# SAM4N_Xplained_Pro_Connectors.net
KiCad netlist of a schematic drawn in Altium Designer
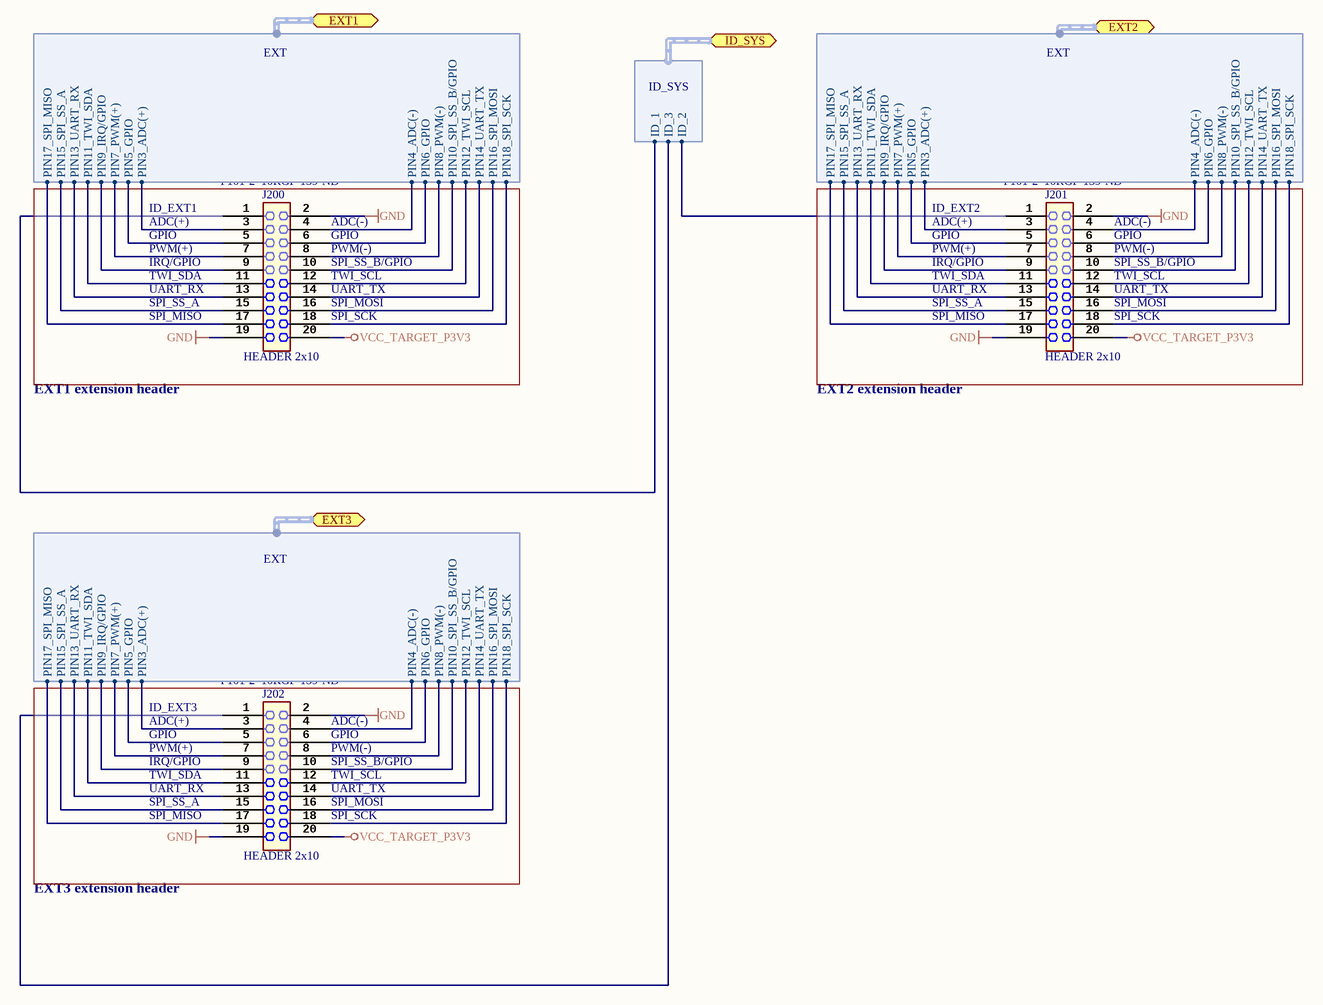
[diagram p0: SAM4N_Xplained_Pro_Connectors.SchDoc]

(export (version "E")
  (design (tool "Eeschema 10.0.6"))
  (components
    (comp (ref "J200")
      (value "HEADER 2x10")
      (footprint "AP8-00622")
      (description "Pin header, 2x10, Right Angle, 2.54mm, THM, Pin In Paste")
      (fields (field (name "ALTIUM_VALUE") "P101-2*10RGF-139-ND") (field (name "MPN") "P101-2*10RGF-139-ND"))
      (libsource (lib "AltiumDbLib") (part "HEADER 2x10"))
    )
    (comp (ref "J201")
      (value "HEADER 2x10")
      (footprint "AP8-00622")
      (description "Pin header, 2x10, Right Angle, 2.54mm, THM, Pin In Paste")
      (fields (field (name "ALTIUM_VALUE") "P101-2*10RGF-139-ND") (field (name "MPN") "P101-2*10RGF-139-ND"))
      (libsource (lib "AltiumDbLib") (part "HEADER 2x10"))
    )
    (comp (ref "J202")
      (value "HEADER 2x10")
      (footprint "AP8-00622")
      (description "Pin header, 2x10, Right Angle, 2.54mm, THM, Pin In Paste")
      (fields (field (name "ALTIUM_VALUE") "P101-2*10RGF-139-ND") (field (name "MPN") "P101-2*10RGF-139-ND"))
      (libsource (lib "AltiumDbLib") (part "HEADER 2x10"))
    )
  )
  (nets
    (net (code "3") (name "/ID_1") (class "Default")
      (node (ref "J200") (pin "1") (pinfunction "1_1") (pintype "passive"))
    )
    (net (code "4") (name "/ID_2") (class "Default")
      (node (ref "J201") (pin "1") (pinfunction "1_1") (pintype "passive"))
    )
    (net (code "5") (name "/ID_3") (class "Default")
      (node (ref "J202") (pin "1") (pinfunction "1_1") (pintype "passive"))
    )
    (net (code "8") (name "GND") (class "Default")
      (node (ref "J200") (pin "19") (pinfunction "19_19") (pintype "passive"))
      (node (ref "J200") (pin "2") (pinfunction "2_2") (pintype "passive"))
      (node (ref "J201") (pin "19") (pinfunction "19_19") (pintype "passive"))
      (node (ref "J201") (pin "2") (pinfunction "2_2") (pintype "passive"))
      (node (ref "J202") (pin "19") (pinfunction "19_19") (pintype "passive"))
      (node (ref "J202") (pin "2") (pinfunction "2_2") (pintype "passive"))
    )
    (net (code "9") (name "VCC_TARGET_P3V3") (class "Default")
      (node (ref "J200") (pin "20") (pinfunction "20_20") (pintype "passive"))
      (node (ref "J201") (pin "20") (pinfunction "20_20") (pintype "passive"))
      (node (ref "J202") (pin "20") (pinfunction "20_20") (pintype "passive"))
    )
    (net (code "10") (name "unconnected-(J200-Pad3)") (class "Default")
      (node (ref "J200") (pin "3") (pinfunction "3_3") (pintype "passive"))
    )
    (net (code "11") (name "unconnected-(J200-Pad4)") (class "Default")
      (node (ref "J200") (pin "4") (pinfunction "4_4") (pintype "passive"))
    )
    (net (code "12") (name "unconnected-(J200-Pad5)") (class "Default")
      (node (ref "J200") (pin "5") (pinfunction "5_5") (pintype "passive"))
    )
    (net (code "13") (name "unconnected-(J200-Pad6)") (class "Default")
      (node (ref "J200") (pin "6") (pinfunction "6_6") (pintype "passive"))
    )
    (net (code "14") (name "unconnected-(J200-Pad7)") (class "Default")
      (node (ref "J200") (pin "7") (pinfunction "7_7") (pintype "passive"))
    )
    (net (code "15") (name "unconnected-(J200-Pad8)") (class "Default")
      (node (ref "J200") (pin "8") (pinfunction "8_8") (pintype "passive"))
    )
    (net (code "16") (name "unconnected-(J200-Pad9)") (class "Default")
      (node (ref "J200") (pin "9") (pinfunction "9_9") (pintype "passive"))
    )
    (net (code "17") (name "unconnected-(J200-Pad10)") (class "Default")
      (node (ref "J200") (pin "10") (pinfunction "10_10") (pintype "passive"))
    )
    (net (code "18") (name "unconnected-(J200-Pad11)") (class "Default")
      (node (ref "J200") (pin "11") (pinfunction "11_11") (pintype "passive"))
    )
    (net (code "19") (name "unconnected-(J200-Pad12)") (class "Default")
      (node (ref "J200") (pin "12") (pinfunction "12_12") (pintype "passive"))
    )
    (net (code "20") (name "unconnected-(J200-Pad13)") (class "Default")
      (node (ref "J200") (pin "13") (pinfunction "13_13") (pintype "passive"))
    )
    (net (code "21") (name "unconnected-(J200-Pad14)") (class "Default")
      (node (ref "J200") (pin "14") (pinfunction "14_14") (pintype "passive"))
    )
    (net (code "22") (name "unconnected-(J200-Pad15)") (class "Default")
      (node (ref "J200") (pin "15") (pinfunction "15_15") (pintype "passive"))
    )
    (net (code "23") (name "unconnected-(J200-Pad16)") (class "Default")
      (node (ref "J200") (pin "16") (pinfunction "16_16") (pintype "passive"))
    )
    (net (code "24") (name "unconnected-(J200-Pad17)") (class "Default")
      (node (ref "J200") (pin "17") (pinfunction "17_17") (pintype "passive"))
    )
    (net (code "25") (name "unconnected-(J200-Pad18)") (class "Default")
      (node (ref "J200") (pin "18") (pinfunction "18_18") (pintype "passive"))
    )
    (net (code "26") (name "unconnected-(J201-Pad3)") (class "Default")
      (node (ref "J201") (pin "3") (pinfunction "3_3") (pintype "passive"))
    )
    (net (code "27") (name "unconnected-(J201-Pad4)") (class "Default")
      (node (ref "J201") (pin "4") (pinfunction "4_4") (pintype "passive"))
    )
    (net (code "28") (name "unconnected-(J201-Pad5)") (class "Default")
      (node (ref "J201") (pin "5") (pinfunction "5_5") (pintype "passive"))
    )
    (net (code "29") (name "unconnected-(J201-Pad6)") (class "Default")
      (node (ref "J201") (pin "6") (pinfunction "6_6") (pintype "passive"))
    )
    (net (code "30") (name "unconnected-(J201-Pad7)") (class "Default")
      (node (ref "J201") (pin "7") (pinfunction "7_7") (pintype "passive"))
    )
    (net (code "31") (name "unconnected-(J201-Pad8)") (class "Default")
      (node (ref "J201") (pin "8") (pinfunction "8_8") (pintype "passive"))
    )
    (net (code "32") (name "unconnected-(J201-Pad9)") (class "Default")
      (node (ref "J201") (pin "9") (pinfunction "9_9") (pintype "passive"))
    )
    (net (code "33") (name "unconnected-(J201-Pad10)") (class "Default")
      (node (ref "J201") (pin "10") (pinfunction "10_10") (pintype "passive"))
    )
    (net (code "34") (name "unconnected-(J201-Pad11)") (class "Default")
      (node (ref "J201") (pin "11") (pinfunction "11_11") (pintype "passive"))
    )
    (net (code "35") (name "unconnected-(J201-Pad12)") (class "Default")
      (node (ref "J201") (pin "12") (pinfunction "12_12") (pintype "passive"))
    )
    (net (code "36") (name "unconnected-(J201-Pad13)") (class "Default")
      (node (ref "J201") (pin "13") (pinfunction "13_13") (pintype "passive"))
    )
    (net (code "37") (name "unconnected-(J201-Pad14)") (class "Default")
      (node (ref "J201") (pin "14") (pinfunction "14_14") (pintype "passive"))
    )
    (net (code "38") (name "unconnected-(J201-Pad15)") (class "Default")
      (node (ref "J201") (pin "15") (pinfunction "15_15") (pintype "passive"))
    )
    (net (code "39") (name "unconnected-(J201-Pad16)") (class "Default")
      (node (ref "J201") (pin "16") (pinfunction "16_16") (pintype "passive"))
    )
    (net (code "40") (name "unconnected-(J201-Pad17)") (class "Default")
      (node (ref "J201") (pin "17") (pinfunction "17_17") (pintype "passive"))
    )
    (net (code "41") (name "unconnected-(J201-Pad18)") (class "Default")
      (node (ref "J201") (pin "18") (pinfunction "18_18") (pintype "passive"))
    )
    (net (code "42") (name "unconnected-(J202-Pad3)") (class "Default")
      (node (ref "J202") (pin "3") (pinfunction "3_3") (pintype "passive"))
    )
    (net (code "43") (name "unconnected-(J202-Pad4)") (class "Default")
      (node (ref "J202") (pin "4") (pinfunction "4_4") (pintype "passive"))
    )
    (net (code "44") (name "unconnected-(J202-Pad5)") (class "Default")
      (node (ref "J202") (pin "5") (pinfunction "5_5") (pintype "passive"))
    )
    (net (code "45") (name "unconnected-(J202-Pad6)") (class "Default")
      (node (ref "J202") (pin "6") (pinfunction "6_6") (pintype "passive"))
    )
    (net (code "46") (name "unconnected-(J202-Pad7)") (class "Default")
      (node (ref "J202") (pin "7") (pinfunction "7_7") (pintype "passive"))
    )
    (net (code "47") (name "unconnected-(J202-Pad8)") (class "Default")
      (node (ref "J202") (pin "8") (pinfunction "8_8") (pintype "passive"))
    )
    (net (code "48") (name "unconnected-(J202-Pad9)") (class "Default")
      (node (ref "J202") (pin "9") (pinfunction "9_9") (pintype "passive"))
    )
    (net (code "49") (name "unconnected-(J202-Pad10)") (class "Default")
      (node (ref "J202") (pin "10") (pinfunction "10_10") (pintype "passive"))
    )
    (net (code "50") (name "unconnected-(J202-Pad11)") (class "Default")
      (node (ref "J202") (pin "11") (pinfunction "11_11") (pintype "passive"))
    )
    (net (code "51") (name "unconnected-(J202-Pad12)") (class "Default")
      (node (ref "J202") (pin "12") (pinfunction "12_12") (pintype "passive"))
    )
    (net (code "52") (name "unconnected-(J202-Pad13)") (class "Default")
      (node (ref "J202") (pin "13") (pinfunction "13_13") (pintype "passive"))
    )
    (net (code "53") (name "unconnected-(J202-Pad14)") (class "Default")
      (node (ref "J202") (pin "14") (pinfunction "14_14") (pintype "passive"))
    )
    (net (code "54") (name "unconnected-(J202-Pad15)") (class "Default")
      (node (ref "J202") (pin "15") (pinfunction "15_15") (pintype "passive"))
    )
    (net (code "55") (name "unconnected-(J202-Pad16)") (class "Default")
      (node (ref "J202") (pin "16") (pinfunction "16_16") (pintype "passive"))
    )
    (net (code "56") (name "unconnected-(J202-Pad17)") (class "Default")
      (node (ref "J202") (pin "17") (pinfunction "17_17") (pintype "passive"))
    )
    (net (code "57") (name "unconnected-(J202-Pad18)") (class "Default")
      (node (ref "J202") (pin "18") (pinfunction "18_18") (pintype "passive"))
    )
  )
)
